# us__2shc.net
KiCad netlist of a schematic drawn in Altium Designer
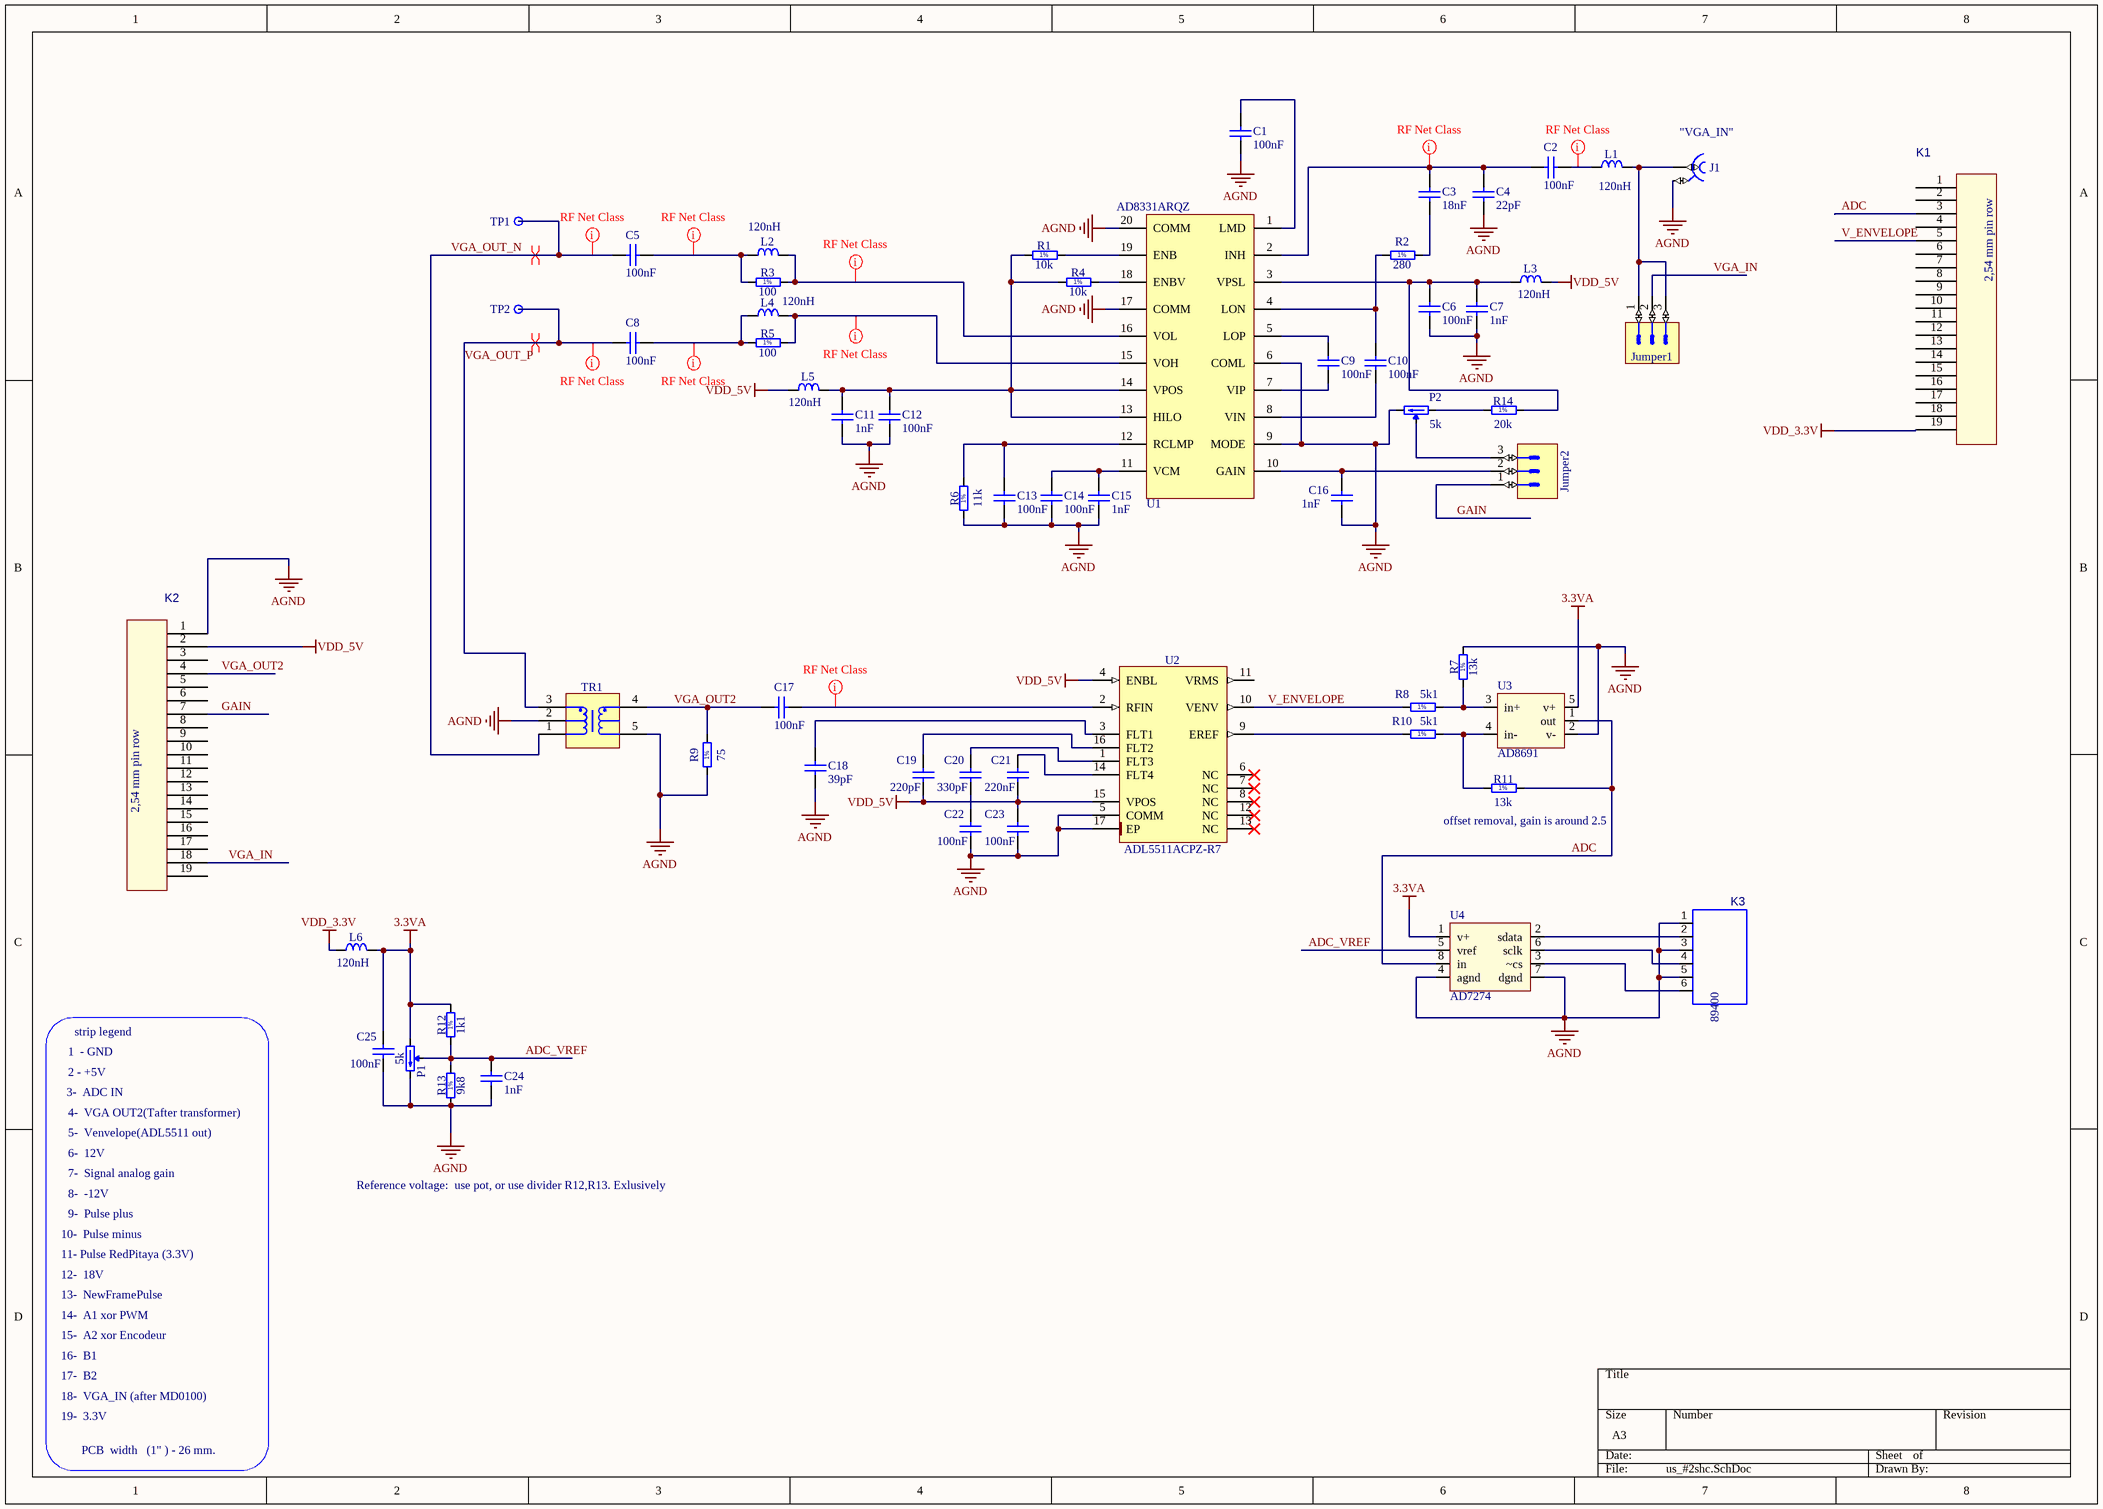
[diagram p0: us_#2shc.SchDoc]

(export (version "E")
  (design (tool "Eeschema 10.0.6"))
  (components
    (comp (ref "C1")
      (value "100nF")
      (footprint "SM0603 _3D_cap")
      (description "Capacitor  0603 inch")
      (fields (field (name "Comment") "cap0603") (field (name "PUBLISHER") "Altium Limited"))
      (libsource (lib "alt_vovan") (part "cap0603"))
    )
    (comp (ref "C2")
      (value "100nF")
      (footprint "SM0603 _3D_cap")
      (description "Capacitor  0603 inch")
      (fields (field (name "Comment") "cap0603") (field (name "PUBLISHER") "Altium Limited"))
      (libsource (lib "alt_vovan") (part "cap0603"))
    )
    (comp (ref "C3")
      (value "18nF")
      (footprint "SM0603 _3D_cap")
      (description "Capacitor  0603 inch")
      (fields (field (name "Comment") "cap0603") (field (name "PUBLISHER") "Altium Limited"))
      (libsource (lib "alt_vovan") (part "cap0603"))
    )
    (comp (ref "C4")
      (value "22pF")
      (footprint "SM0603 _3D_cap")
      (description "Capacitor  0603 inch")
      (fields (field (name "Comment") "cap0603") (field (name "PUBLISHER") "Altium Limited"))
      (libsource (lib "alt_vovan") (part "cap0603"))
    )
    (comp (ref "C5")
      (value "100nF")
      (footprint "SM0603 _3D_cap")
      (description "Capacitor  0603 inch")
      (fields (field (name "Comment") "cap0603") (field (name "PUBLISHER") "Altium Limited"))
      (libsource (lib "alt_vovan") (part "cap0603"))
    )
    (comp (ref "C6")
      (value "100nF")
      (footprint "SM0603 _3D_cap")
      (description "Capacitor  0603 inch")
      (fields (field (name "Comment") "cap0603") (field (name "PUBLISHER") "Altium Limited"))
      (libsource (lib "alt_vovan") (part "cap0603"))
    )
    (comp (ref "C7")
      (value "1nF")
      (footprint "SM0603 _3D_cap")
      (description "Capacitor  0603 inch")
      (fields (field (name "Comment") "cap0603") (field (name "PUBLISHER") "Altium Limited"))
      (libsource (lib "alt_vovan") (part "cap0603"))
    )
    (comp (ref "C8")
      (value "100nF")
      (footprint "SM0603 _3D_cap")
      (description "Capacitor  0603 inch")
      (fields (field (name "Comment") "cap0603") (field (name "PUBLISHER") "Altium Limited"))
      (libsource (lib "alt_vovan") (part "cap0603"))
    )
    (comp (ref "C9")
      (value "100nF")
      (footprint "SM0603 _3D_cap")
      (description "Capacitor  0603 inch")
      (fields (field (name "Comment") "cap0603") (field (name "PUBLISHER") "Altium Limited"))
      (libsource (lib "alt_vovan") (part "cap0603"))
    )
    (comp (ref "C10")
      (value "100nF")
      (footprint "SM0603 _3D_cap")
      (description "Capacitor  0603 inch")
      (fields (field (name "Comment") "cap0603") (field (name "PUBLISHER") "Altium Limited"))
      (libsource (lib "alt_vovan") (part "cap0603"))
    )
    (comp (ref "C11")
      (value "1nF")
      (footprint "SM0603 _3D_cap")
      (description "Capacitor  0603 inch")
      (fields (field (name "Comment") "cap0603") (field (name "PUBLISHER") "Altium Limited"))
      (libsource (lib "alt_vovan") (part "cap0603"))
    )
    (comp (ref "C12")
      (value "100nF")
      (footprint "SM0603 _3D_cap")
      (description "Capacitor  0603 inch")
      (fields (field (name "Comment") "cap0603") (field (name "PUBLISHER") "Altium Limited"))
      (libsource (lib "alt_vovan") (part "cap0603"))
    )
    (comp (ref "C13")
      (value "100nF")
      (footprint "SM0603 _3D_cap")
      (description "Capacitor  0603 inch")
      (fields (field (name "Comment") "cap0603") (field (name "PUBLISHER") "Altium Limited"))
      (libsource (lib "alt_vovan") (part "cap0603"))
    )
    (comp (ref "C14")
      (value "100nF")
      (footprint "SM0603 _3D_cap")
      (description "Capacitor  0603 inch")
      (fields (field (name "Comment") "cap0603") (field (name "PUBLISHER") "Altium Limited"))
      (libsource (lib "alt_vovan") (part "cap0603"))
    )
    (comp (ref "C15")
      (value "1nF")
      (footprint "SM0603 _3D_cap")
      (description "Capacitor  0603 inch")
      (fields (field (name "Comment") "cap0603") (field (name "PUBLISHER") "Altium Limited"))
      (libsource (lib "alt_vovan") (part "cap0603"))
    )
    (comp (ref "C16")
      (value "1nF")
      (footprint "SM0603 _3D_cap")
      (description "Capacitor  0603 inch")
      (fields (field (name "Comment") "cap0603") (field (name "PUBLISHER") "Altium Limited"))
      (libsource (lib "alt_vovan") (part "cap0603"))
    )
    (comp (ref "C17")
      (value "100nF")
      (footprint "SM0603 _3D_cap")
      (description "Capacitor  0603 inch")
      (fields (field (name "Comment") "cap0603") (field (name "PUBLISHER") "Altium Limited"))
      (libsource (lib "alt_vovan") (part "cap0603"))
    )
    (comp (ref "C18")
      (value "39pF")
      (footprint "SM0603 _3D_cap")
      (description "Capacitor  0603 inch")
      (fields (field (name "Comment") "cap0603") (field (name "PUBLISHER") "Altium Limited"))
      (libsource (lib "alt_vovan") (part "cap0603"))
    )
    (comp (ref "C19")
      (value "220pF")
      (footprint "SM0603 _3D_cap")
      (description "Capacitor  0603 inch")
      (fields (field (name "Comment") "cap0603") (field (name "PUBLISHER") "Altium Limited"))
      (libsource (lib "alt_vovan") (part "cap0603"))
    )
    (comp (ref "C20")
      (value "330pF")
      (footprint "SM0603 _3D_cap")
      (description "Capacitor  0603 inch")
      (fields (field (name "Comment") "cap0603") (field (name "PUBLISHER") "Altium Limited"))
      (libsource (lib "alt_vovan") (part "cap0603"))
    )
    (comp (ref "C21")
      (value "220nF")
      (footprint "SM0603 _3D_cap")
      (description "Capacitor  0603 inch")
      (fields (field (name "Comment") "cap0603") (field (name "PUBLISHER") "Altium Limited"))
      (libsource (lib "alt_vovan") (part "cap0603"))
    )
    (comp (ref "C22")
      (value "100nF")
      (footprint "SM0603 _3D_cap")
      (description "Capacitor  0603 inch")
      (fields (field (name "Comment") "cap0603") (field (name "PUBLISHER") "Altium Limited"))
      (libsource (lib "alt_vovan") (part "cap0603"))
    )
    (comp (ref "C23")
      (value "100nF")
      (footprint "SM0603 _3D_cap")
      (description "Capacitor  0603 inch")
      (fields (field (name "Comment") "cap0603") (field (name "PUBLISHER") "Altium Limited"))
      (libsource (lib "alt_vovan") (part "cap0603"))
    )
    (comp (ref "C24")
      (value "1nF")
      (footprint "SM0603 _3D_cap")
      (description "Capacitor  0603 inch")
      (fields (field (name "Comment") "cap0603") (field (name "PUBLISHER") "Altium Limited"))
      (libsource (lib "alt_vovan") (part "cap0603"))
    )
    (comp (ref "C25")
      (value "100nF")
      (footprint "SM0603 _3D_cap")
      (description "Capacitor  0603 inch")
      (fields (field (name "Comment") "cap0603") (field (name "PUBLISHER") "Altium Limited"))
      (libsource (lib "alt_vovan") (part "cap0603"))
    )
    (comp (ref "J1")
      (value "SMA")
      (footprint "AMPHENOL_132357-11")
      (fields
        (field (name "PART NUMBER") "AMPHENOL_132357-11")
        (field (name "MANUFACTURER") "AMPHENOL")
        (field (name "MANUFACTURER PART NUMBER") "132357-11")
        (field (name "AUTHOR") "CERN DEM JLC")
      )
      (libsource (lib "echOpen_ADC_Card") (part "Coax_1Female_1Shield"))
    )
    (comp (ref "Jumper1")
      (value "~")
      (footprint "SULLINS_GRPB031VWVN")
      (description "Connector 3 Male")
      (fields
        (field (name "PART NUMBER") "SULLINS_GRPB031VWVN")
        (field (name "MANUFACTURER") "SULLINS")
        (field (name "AUTHOR") "S. Jafar")
      )
      (libsource (lib "Sof-Connectors") (part "Connector 3 Male"))
    )
    (comp (ref "Jumper2")
      (value "~")
      (footprint "SULLINS_GRPB031VWVN")
      (description "Connector 3 Male")
      (fields
        (field (name "PART NUMBER") "SULLINS_GRPB031VWVN")
        (field (name "MANUFACTURER") "SULLINS")
        (field (name "AUTHOR") "S. Jafar")
      )
      (libsource (lib "") (part "Connector 3 Male_1"))
    )
    (comp (ref "K1")
      (value "PLS_2.54mm-19")
      (footprint "PLS_2.54mm-19")
      (libsource (lib "alt_vovan") (part "PLS_2.54mm-19"))
    )
    (comp (ref "K2")
      (value "PLS_2.54mm-19")
      (footprint "PLS_2.54mm-19")
      (libsource (lib "") (part "PLS_2.54mm-19_1"))
    )
    (comp (ref "K3")
      (value "Molex_89400_061")
      (footprint "Molex_89400-061")
      (description "6 pin vertical 2mm")
      (libsource (lib "alt_vovan") (part "Molex_89400_061"))
    )
    (comp (ref "L1")
      (value "75R@100MHz")
      (footprint "SM_0805_INDUCTANCE _3D")
      (description "chip inductance")
      (fields
        (field (name "PART NUMBER") "IND0805_MURATA_BLM21BB750SN1D")
        (field (name "POWER") "700mA")
        (field (name "AUTHOR") "S. Jafar")
      )
      (libsource (lib "alt_vovan") (part "Ind_Chip"))
    )
    (comp (ref "L2")
      (value "75R@100MHz")
      (footprint "SM_0805_INDUCTANCE _3D")
      (description "chip inductance")
      (fields
        (field (name "PART NUMBER") "IND0805_MURATA_BLM21BB750SN1D")
        (field (name "POWER") "700mA")
        (field (name "AUTHOR") "S. Jafar")
      )
      (libsource (lib "alt_vovan") (part "Ind_Chip"))
    )
    (comp (ref "L3")
      (value "75R@100MHz")
      (footprint "SM_0805_INDUCTANCE _3D")
      (description "chip inductance")
      (fields
        (field (name "PART NUMBER") "IND0805_MURATA_BLM21BB750SN1D")
        (field (name "POWER") "700mA")
        (field (name "AUTHOR") "S. Jafar")
      )
      (libsource (lib "alt_vovan") (part "Ind_Chip"))
    )
    (comp (ref "L4")
      (value "75R@100MHz")
      (footprint "SM_0805_INDUCTANCE _3D")
      (description "chip inductance")
      (fields
        (field (name "PART NUMBER") "IND0805_MURATA_BLM21BB750SN1D")
        (field (name "POWER") "700mA")
        (field (name "AUTHOR") "S. Jafar")
      )
      (libsource (lib "alt_vovan") (part "Ind_Chip"))
    )
    (comp (ref "L5")
      (value "75R@100MHz")
      (footprint "SM_0805_INDUCTANCE _3D")
      (description "chip inductance")
      (fields
        (field (name "PART NUMBER") "IND0805_MURATA_BLM21BB750SN1D")
        (field (name "POWER") "700mA")
        (field (name "AUTHOR") "S. Jafar")
      )
      (libsource (lib "alt_vovan") (part "Ind_Chip"))
    )
    (comp (ref "L6")
      (value "75R@100MHz")
      (footprint "SM_0805_INDUCTANCE _3D")
      (description "chip inductance")
      (fields
        (field (name "PART NUMBER") "IND0805_MURATA_BLM21BB750SN1D")
        (field (name "POWER") "700mA")
        (field (name "AUTHOR") "S. Jafar")
      )
      (libsource (lib "alt_vovan") (part "Ind_Chip"))
    )
    (comp (ref "P1")
      (value "5k")
      (footprint "TRIM_BOURNS_3223W")
      (description "Trimming Potentiometer")
      (fields
        (field (name "PART NUMBER") "TRIM_11T_5K_BOURNS_3223W-1-502E")
        (field (name "POWER") "0.125W")
        (field (name "AUTHOR") "CERN DEM JLC")
      )
      (libsource (lib "echOpen_ADC_Card") (part "Trimming Potentiometer"))
    )
    (comp (ref "P2")
      (value "5k")
      (footprint "TRIM_BOURNS_3223W")
      (description "Trimming Potentiometer")
      (fields
        (field (name "PART NUMBER") "TRIM_11T_5K_BOURNS_3223W-1-502E")
        (field (name "POWER") "0.125W")
        (field (name "AUTHOR") "CERN DEM JLC")
      )
      (libsource (lib "echOpen_ADC_Card") (part "Trimming Potentiometer"))
    )
    (comp (ref "R1")
      (value "10k")
      (footprint "SM0603_3D_res")
      (description "Res_0603_1%_EU")
      (fields
        (field (name "PART NUMBER") "R1206_4K7_1%_0.25W_100PPM")
        (field (name "POWER") "0.25W")
        (field (name "AUTHOR") "CERN DEM JLC")
      )
      (libsource (lib "alt_vovan") (part "Res_0603_1%_EU"))
    )
    (comp (ref "R2")
      (value "280")
      (footprint "SM0603_3D_res")
      (description "Res_0603_1%_EU")
      (fields
        (field (name "PART NUMBER") "R1206_4K7_1%_0.25W_100PPM")
        (field (name "POWER") "0.25W")
        (field (name "AUTHOR") "CERN DEM JLC")
      )
      (libsource (lib "alt_vovan") (part "Res_0603_1%_EU"))
    )
    (comp (ref "R3")
      (value "100")
      (footprint "SM0603_3D_res")
      (description "Res_0603_1%_EU")
      (fields
        (field (name "PART NUMBER") "R1206_4K7_1%_0.25W_100PPM")
        (field (name "POWER") "0.25W")
        (field (name "AUTHOR") "CERN DEM JLC")
      )
      (libsource (lib "alt_vovan") (part "Res_0603_1%_EU"))
    )
    (comp (ref "R4")
      (value "10k")
      (footprint "SM0603_3D_res")
      (description "Res_0603_1%_EU")
      (fields
        (field (name "PART NUMBER") "R1206_4K7_1%_0.25W_100PPM")
        (field (name "POWER") "0.25W")
        (field (name "AUTHOR") "CERN DEM JLC")
      )
      (libsource (lib "alt_vovan") (part "Res_0603_1%_EU"))
    )
    (comp (ref "R5")
      (value "100")
      (footprint "SM0603_3D_res")
      (description "Res_0603_1%_EU")
      (fields
        (field (name "PART NUMBER") "R1206_4K7_1%_0.25W_100PPM")
        (field (name "POWER") "0.25W")
        (field (name "AUTHOR") "CERN DEM JLC")
      )
      (libsource (lib "alt_vovan") (part "Res_0603_1%_EU"))
    )
    (comp (ref "R6")
      (value "11k")
      (footprint "SM0603_3D_res")
      (description "Res_0603_1%_EU")
      (fields
        (field (name "PART NUMBER") "R1206_4K7_1%_0.25W_100PPM")
        (field (name "POWER") "0.25W")
        (field (name "AUTHOR") "CERN DEM JLC")
      )
      (libsource (lib "alt_vovan") (part "Res_0603_1%_EU"))
    )
    (comp (ref "R7")
      (value "13k")
      (footprint "SM0603_3D_res")
      (description "Res_0603_1%_EU")
      (fields
        (field (name "PART NUMBER") "R1206_4K7_1%_0.25W_100PPM")
        (field (name "POWER") "0.25W")
        (field (name "AUTHOR") "CERN DEM JLC")
      )
      (libsource (lib "alt_vovan") (part "Res_0603_1%_EU"))
    )
    (comp (ref "R8")
      (value "5k1")
      (footprint "SM0603_3D_res")
      (description "Res_0603_1%_EU")
      (fields
        (field (name "PART NUMBER") "R1206_4K7_1%_0.25W_100PPM")
        (field (name "POWER") "0.25W")
        (field (name "AUTHOR") "CERN DEM JLC")
      )
      (libsource (lib "alt_vovan") (part "Res_0603_1%_EU"))
    )
    (comp (ref "R9")
      (value "75")
      (footprint "SM0603_3D_res")
      (description "Res_0603_1%_EU")
      (fields
        (field (name "PART NUMBER") "R1206_4K7_1%_0.25W_100PPM")
        (field (name "POWER") "0.25W")
        (field (name "AUTHOR") "CERN DEM JLC")
      )
      (libsource (lib "alt_vovan") (part "Res_0603_1%_EU"))
    )
    (comp (ref "R10")
      (value "5k1")
      (footprint "SM0603_3D_res")
      (description "Res_0603_1%_EU")
      (fields
        (field (name "PART NUMBER") "R1206_4K7_1%_0.25W_100PPM")
        (field (name "POWER") "0.25W")
        (field (name "AUTHOR") "CERN DEM JLC")
      )
      (libsource (lib "alt_vovan") (part "Res_0603_1%_EU"))
    )
    (comp (ref "R11")
      (value "13k")
      (footprint "SM0603_3D_res")
      (description "Res_0603_1%_EU")
      (fields
        (field (name "PART NUMBER") "R1206_4K7_1%_0.25W_100PPM")
        (field (name "POWER") "0.25W")
        (field (name "AUTHOR") "CERN DEM JLC")
      )
      (libsource (lib "alt_vovan") (part "Res_0603_1%_EU"))
    )
    (comp (ref "R12")
      (value "1k1")
      (footprint "SM0603_3D_res")
      (description "Res_0603_1%_EU")
      (fields
        (field (name "PART NUMBER") "R1206_4K7_1%_0.25W_100PPM")
        (field (name "POWER") "0.25W")
        (field (name "AUTHOR") "CERN DEM JLC")
      )
      (libsource (lib "alt_vovan") (part "Res_0603_1%_EU"))
    )
    (comp (ref "R13")
      (value "9k8")
      (footprint "SM0603_3D_res")
      (description "Res_0603_1%_EU")
      (fields
        (field (name "PART NUMBER") "R1206_4K7_1%_0.25W_100PPM")
        (field (name "POWER") "0.25W")
        (field (name "AUTHOR") "CERN DEM JLC")
      )
      (libsource (lib "alt_vovan") (part "Res_0603_1%_EU"))
    )
    (comp (ref "R14")
      (value "20k")
      (footprint "SM0603_3D_res")
      (description "Res_0603_1%_EU")
      (fields
        (field (name "PART NUMBER") "R1206_4K7_1%_0.25W_100PPM")
        (field (name "POWER") "0.25W")
        (field (name "AUTHOR") "CERN DEM JLC")
      )
      (libsource (lib "alt_vovan") (part "Res_0603_1%_EU"))
    )
    (comp (ref "TP1")
      (value "Test Point")
      (footprint "NICOMATIC_C12000B")
      (fields
        (field (name "PART NUMBER") "NICOMATIC_C12000B")
        (field (name "MANUFACTURER") "NICOMATIC")
        (field (name "MANUFACTURER PART NUMBER") "C12000B")
        (field (name "AUTHOR") "CERN DEM JLC")
      )
      (libsource (lib "Sof-Connectors") (part "Test Point"))
    )
    (comp (ref "TP2")
      (value "Test Point")
      (footprint "NICOMATIC_C12000B")
      (fields
        (field (name "PART NUMBER") "NICOMATIC_C12000B")
        (field (name "MANUFACTURER") "NICOMATIC")
        (field (name "MANUFACTURER PART NUMBER") "C12000B")
        (field (name "AUTHOR") "CERN DEM JLC")
      )
      (libsource (lib "Sof-Connectors") (part "Test Point"))
    )
    (comp (ref "TR1")
      (value "1:1")
      (footprint "alt_vovan:Pulse_CX2041NL")
      (description "75 Ohm 0.05 to 300MHz RF Transformers")
      (fields
        (field (name "PART NUMBER") "XFMR_MINI-CIRCUITS_T1-6T-KK81")
        (field (name "MANUFACTURER") "MINI-CIRCUITS")
        (field (name "AUTHOR") "S. Jafar")
      )
      (libsource (lib "alt2017") (part "Pulse_CX2041NL"))
    )
    (comp (ref "U1")
      (value "AD8331ARQZ")
      (footprint "SOP64P600X175-20N")
      (fields (field (name "MANUFACTURER") "Analog Devices") (field (name "AUTHOR") "S. Jafar"))
      (libsource (lib "Sof-ICs And Semiconductors") (part "AD8331"))
    )
    (comp (ref "U2")
      (value "ADL5511ACPZ-R7")
      (footprint "QFN50P300X300X80-17N-S175")
      (description "DC to 6 GHz Envelope and TruPwr RMS Detector")
      (fields (field (name "MANUFACTURER") "ANALOG DEVICES") (field (name "AUTHOR") "CERN DEM JLC"))
      (libsource (lib "Sof-ICs And Semiconductors") (part "ADL5511"))
    )
    (comp (ref "U3")
      (value "AD8691")
      (footprint "TSOT-5(RT-5)")
      (libsource (lib "alt_vovan") (part "OpAmp_TSOT5"))
    )
    (comp (ref "U4")
      (value "AD7274")
      (footprint "RM-8")
      (description "adc serial")
      (libsource (lib "alt_vovan") (part "AD7274"))
    )
  )
  (nets
    (net (code "1") (name "/ADC") (class "Default")
      (node (ref "K1") (pin "3") (pinfunction "3_3") (pintype "passive"))
      (node (ref "R11") (pin "2") (pinfunction "2_2") (pintype "passive"))
      (node (ref "U3") (pin "1") (pinfunction "out_1") (pintype "passive"))
      (node (ref "U4") (pin "8") (pinfunction "in_8") (pintype "passive"))
    )
    (net (code "2") (name "/ADC_VREF") (class "Default")
      (node (ref "C24") (pin "2") (pinfunction "2_2") (pintype "passive"))
      (node (ref "P1") (pin "2") (pinfunction "W_2") (pintype "passive"))
      (node (ref "R12") (pin "1") (pinfunction "1_1") (pintype "passive"))
      (node (ref "R13") (pin "2") (pinfunction "2_2") (pintype "passive"))
      (node (ref "U4") (pin "5") (pinfunction "vref_5") (pintype "passive"))
    )
    (net (code "3") (name "/GAIN") (class "Default")
      (node (ref "Jumper2") (pin "1") (pinfunction "1_1") (pintype "bidirectional"))
      (node (ref "K2") (pin "7") (pinfunction "7_7") (pintype "passive"))
    )
    (net (code "4") (name "/VGA_IN") (class "Default")
      (node (ref "Jumper1") (pin "2") (pinfunction "2_2") (pintype "bidirectional"))
      (node (ref "K2") (pin "18") (pinfunction "18_18") (pintype "passive"))
    )
    (net (code "5") (name "/VGA_OUT2") (class "Default")
      (node (ref "C17") (pin "1") (pinfunction "1_1") (pintype "passive"))
      (node (ref "K2") (pin "4") (pinfunction "4_4") (pintype "passive"))
      (node (ref "R9") (pin "2") (pinfunction "2_2") (pintype "passive"))
      (node (ref "TR1") (pin "4") (pinfunction "SDOT_4") (pintype "passive"))
    )
    (net (code "6") (name "/VGA_OUT_N") (class "Default")
      (node (ref "C5") (pin "1") (pinfunction "1_1") (pintype "passive"))
      (node (ref "TP1") (pin "1") (pinfunction "1_1") (pintype "bidirectional"))
      (node (ref "TR1") (pin "1") (pinfunction "P_1") (pintype "passive"))
    )
    (net (code "7") (name "/VGA_OUT_P") (class "Default")
      (node (ref "C8") (pin "2") (pinfunction "2_2") (pintype "passive"))
      (node (ref "TP2") (pin "1") (pinfunction "1_1") (pintype "bidirectional"))
      (node (ref "TR1") (pin "3") (pinfunction "PDOT_3") (pintype "passive"))
    )
    (net (code "8") (name "/V_ENVELOPE") (class "Default")
      (node (ref "K1") (pin "5") (pinfunction "5_5") (pintype "passive"))
      (node (ref "R8") (pin "1") (pinfunction "1_1") (pintype "passive"))
      (node (ref "U2") (pin "10") (pinfunction "VENV_10") (pintype "output"))
    )
    (net (code "9") (name "3.3VA") (class "Default")
      (node (ref "C25") (pin "2") (pinfunction "2_2") (pintype "passive"))
      (node (ref "L6") (pin "2") (pinfunction "2_2") (pintype "passive"))
      (node (ref "P1") (pin "1") (pinfunction "CCW_1") (pintype "passive"))
      (node (ref "R12") (pin "2") (pinfunction "2_2") (pintype "passive"))
      (node (ref "U3") (pin "5") (pinfunction "v+_5") (pintype "passive"))
      (node (ref "U4") (pin "1") (pinfunction "v+_1") (pintype "passive"))
    )
    (net (code "10") (name "AGND") (class "Default")
      (node (ref "C1") (pin "1") (pinfunction "1_1") (pintype "passive"))
      (node (ref "C11") (pin "1") (pinfunction "1_1") (pintype "passive"))
      (node (ref "C12") (pin "1") (pinfunction "1_1") (pintype "passive"))
      (node (ref "C13") (pin "1") (pinfunction "1_1") (pintype "passive"))
      (node (ref "C14") (pin "1") (pinfunction "1_1") (pintype "passive"))
      (node (ref "C15") (pin "1") (pinfunction "1_1") (pintype "passive"))
      (node (ref "C16") (pin "1") (pinfunction "1_1") (pintype "passive"))
      (node (ref "C18") (pin "1") (pinfunction "1_1") (pintype "passive"))
      (node (ref "C22") (pin "1") (pinfunction "1_1") (pintype "passive"))
      (node (ref "C23") (pin "1") (pinfunction "1_1") (pintype "passive"))
      (node (ref "C24") (pin "1") (pinfunction "1_1") (pintype "passive"))
      (node (ref "C25") (pin "1") (pinfunction "1_1") (pintype "passive"))
      (node (ref "C4") (pin "1") (pinfunction "1_1") (pintype "passive"))
      (node (ref "C6") (pin "1") (pinfunction "1_1") (pintype "passive"))
      (node (ref "C7") (pin "1") (pinfunction "1_1") (pintype "passive"))
      (node (ref "J1") (pin "2") (pinfunction "2_2") (pintype "bidirectional"))
      (node (ref "K2") (pin "1") (pinfunction "1_1") (pintype "passive"))
      (node (ref "K3") (pin "1") (pinfunction "1_1") (pintype "passive"))
      (node (ref "K3") (pin "3") (pinfunction "3_3") (pintype "passive"))
      (node (ref "K3") (pin "5") (pinfunction "5_5") (pintype "passive"))
      (node (ref "P1") (pin "3") (pinfunction "CW_3") (pintype "passive"))
      (node (ref "P2") (pin "3") (pinfunction "CW_3") (pintype "passive"))
      (node (ref "R13") (pin "1") (pinfunction "1_1") (pintype "passive"))
      (node (ref "R6") (pin "1") (pinfunction "1_1") (pintype "passive"))
      (node (ref "R7") (pin "2") (pinfunction "2_2") (pintype "passive"))
      (node (ref "R9") (pin "1") (pinfunction "1_1") (pintype "passive"))
      (node (ref "TR1") (pin "2") (pinfunction "NC_2") (pintype "passive"))
      (node (ref "TR1") (pin "5") (pinfunction "6_5") (pintype "passive"))
      (node (ref "U1") (pin "17") (pinfunction "COMM_17") (pintype "passive"))
      (node (ref "U1") (pin "20") (pinfunction "COMM_20") (pintype "passive"))
      (node (ref "U1") (pin "6") (pinfunction "COML_6") (pintype "passive"))
      (node (ref "U1") (pin "9") (pinfunction "MODE_9") (pintype "passive"))
      (node (ref "U2") (pin "17") (pinfunction "EP_17") (pintype "power_in"))
      (node (ref "U2") (pin "5") (pinfunction "COMM_5") (pintype "power_in"))
      (node (ref "U3") (pin "2") (pinfunction "v-_2") (pintype "passive"))
      (node (ref "U4") (pin "4") (pinfunction "agnd_4") (pintype "passive"))
      (node (ref "U4") (pin "7") (pinfunction "dgnd_7") (pintype "passive"))
    )
    (net (code "11") (name "Net-(C2-Pad2)") (class "Default")
      (node (ref "C2") (pin "2") (pinfunction "2_2") (pintype "passive"))
      (node (ref "L1") (pin "1") (pinfunction "1_1") (pintype "passive"))
    )
    (net (code "12") (name "Net-(C3-Pad1)") (class "Default")
      (node (ref "C3") (pin "1") (pinfunction "1_1") (pintype "passive"))
      (node (ref "R2") (pin "2") (pinfunction "2_2") (pintype "passive"))
    )
    (net (code "13") (name "Net-(C5-Pad2)") (class "Default")
      (node (ref "C5") (pin "2") (pinfunction "2_2") (pintype "passive"))
      (node (ref "L2") (pin "1") (pinfunction "1_1") (pintype "passive"))
      (node (ref "R3") (pin "1") (pinfunction "1_1") (pintype "passive"))
    )
    (net (code "14") (name "Net-(C8-Pad1)") (class "Default")
      (node (ref "C8") (pin "1") (pinfunction "1_1") (pintype "passive"))
      (node (ref "L4") (pin "1") (pinfunction "1_1") (pintype "passive"))
      (node (ref "R5") (pin "1") (pinfunction "1_1") (pintype "passive"))
    )
    (net (code "15") (name "Net-(C20-Pad1)") (class "Default")
      (node (ref "C20") (pin "1") (pinfunction "1_1") (pintype "passive"))
      (node (ref "C22") (pin "2") (pinfunction "2_2") (pintype "passive"))
    )
    (net (code "16") (name "Net-(J1-Pad1)") (class "Default")
      (node (ref "J1") (pin "1") (pinfunction "1_1") (pintype "bidirectional"))
      (node (ref "Jumper1") (pin "1") (pinfunction "1_1") (pintype "bidirectional"))
      (node (ref "Jumper1") (pin "3") (pinfunction "3_3") (pintype "bidirectional"))
      (node (ref "L1") (pin "2") (pinfunction "2_2") (pintype "passive"))
    )
    (net (code "17") (name "Net-(P2-CCW)") (class "Default")
      (node (ref "P2") (pin "1") (pinfunction "CCW_1") (pintype "passive"))
      (node (ref "R14") (pin "1") (pinfunction "1_1") (pintype "passive"))
    )
    (net (code "18") (name "Net-(P2-W)") (class "Default")
      (node (ref "Jumper2") (pin "3") (pinfunction "3_3") (pintype "bidirectional"))
      (node (ref "P2") (pin "2") (pinfunction "W_2") (pintype "passive"))
    )
    (net (code "19") (name "Net-(U1-ENB)") (class "Default")
      (node (ref "R1") (pin "2") (pinfunction "2_2") (pintype "passive"))
      (node (ref "U1") (pin "19") (pinfunction "ENB_19") (pintype "passive"))
    )
    (net (code "20") (name "Net-(U1-ENBV)") (class "Default")
      (node (ref "R4") (pin "2") (pinfunction "2_2") (pintype "passive"))
      (node (ref "U1") (pin "18") (pinfunction "ENBV_18") (pintype "passive"))
    )
    (net (code "21") (name "Net-(U1-GAIN)") (class "Default")
      (node (ref "C16") (pin "2") (pinfunction "2_2") (pintype "passive"))
      (node (ref "Jumper2") (pin "2") (pinfunction "2_2") (pintype "bidirectional"))
      (node (ref "U1") (pin "10") (pinfunction "GAIN_10") (pintype "passive"))
    )
    (net (code "22") (name "Net-(U1-HILO)") (class "Default")
      (node (ref "C11") (pin "2") (pinfunction "2_2") (pintype "passive"))
      (node (ref "C12") (pin "2") (pinfunction "2_2") (pintype "passive"))
      (node (ref "L5") (pin "2") (pinfunction "2_2") (pintype "passive"))
      (node (ref "R1") (pin "1") (pinfunction "1_1") (pintype "passive"))
      (node (ref "R4") (pin "1") (pinfunction "1_1") (pintype "passive"))
      (node (ref "U1") (pin "13") (pinfunction "HILO_13") (pintype "passive"))
      (node (ref "U1") (pin "14") (pinfunction "VPOS_14") (pintype "passive"))
    )
    (net (code "23") (name "Net-(U1-INH)") (class "Default")
      (node (ref "C2") (pin "1") (pinfunction "1_1") (pintype "passive"))
      (node (ref "C3") (pin "2") (pinfunction "2_2") (pintype "passive"))
      (node (ref "C4") (pin "2") (pinfunction "2_2") (pintype "passive"))
      (node (ref "U1") (pin "2") (pinfunction "INH_2") (pintype "passive"))
    )
    (net (code "24") (name "Net-(U1-LMD)") (class "Default")
      (node (ref "C1") (pin "2") (pinfunction "2_2") (pintype "passive"))
      (node (ref "U1") (pin "1") (pinfunction "LMD_1") (pintype "passive"))
    )
    (net (code "25") (name "Net-(U1-LON)") (class "Default")
      (node (ref "C10") (pin "2") (pinfunction "2_2") (pintype "passive"))
      (node (ref "R2") (pin "1") (pinfunction "1_1") (pintype "passive"))
      (node (ref "U1") (pin "4") (pinfunction "LON_4") (pintype "passive"))
    )
    (net (code "26") (name "Net-(U1-LOP)") (class "Default")
      (node (ref "C9") (pin "2") (pinfunction "2_2") (pintype "passive"))
      (node (ref "U1") (pin "5") (pinfunction "LOP_5") (pintype "passive"))
    )
    (net (code "27") (name "Net-(U1-RCLMP)") (class "Default")
      (node (ref "C13") (pin "2") (pinfunction "2_2") (pintype "passive"))
      (node (ref "R6") (pin "2") (pinfunction "2_2") (pintype "passive"))
      (node (ref "U1") (pin "12") (pinfunction "RCLMP_12") (pintype "passive"))
    )
    (net (code "28") (name "Net-(U1-VCM)") (class "Default")
      (node (ref "C14") (pin "2") (pinfunction "2_2") (pintype "passive"))
      (node (ref "C15") (pin "2") (pinfunction "2_2") (pintype "passive"))
      (node (ref "U1") (pin "11") (pinfunction "VCM_11") (pintype "passive"))
    )
    (net (code "29") (name "Net-(U1-VIN)") (class "Default")
      (node (ref "C10") (pin "1") (pinfunction "1_1") (pintype "passive"))
      (node (ref "U1") (pin "8") (pinfunction "VIN_8") (pintype "passive"))
    )
    (net (code "30") (name "Net-(U1-VIP)") (class "Default")
      (node (ref "C9") (pin "1") (pinfunction "1_1") (pintype "passive"))
      (node (ref "U1") (pin "7") (pinfunction "VIP_7") (pintype "passive"))
    )
    (net (code "31") (name "Net-(U1-VOH)") (class "Default")
      (node (ref "L4") (pin "2") (pinfunction "2_2") (pintype "passive"))
      (node (ref "R5") (pin "2") (pinfunction "2_2") (pintype "passive"))
      (node (ref "U1") (pin "15") (pinfunction "VOH_15") (pintype "passive"))
    )
    (net (code "32") (name "Net-(U1-VOL)") (class "Default")
      (node (ref "L2") (pin "2") (pinfunction "2_2") (pintype "passive"))
      (node (ref "R3") (pin "2") (pinfunction "2_2") (pintype "passive"))
      (node (ref "U1") (pin "16") (pinfunction "VOL_16") (pintype "passive"))
    )
    (net (code "33") (name "Net-(U1-VPSL)") (class "Default")
      (node (ref "C6") (pin "2") (pinfunction "2_2") (pintype "passive"))
      (node (ref "C7") (pin "2") (pinfunction "2_2") (pintype "passive"))
      (node (ref "L3") (pin "1") (pinfunction "1_1") (pintype "passive"))
      (node (ref "R14") (pin "2") (pinfunction "2_2") (pintype "passive"))
      (node (ref "U1") (pin "3") (pinfunction "VPSL_3") (pintype "passive"))
    )
    (net (code "34") (name "Net-(U2-EREF)") (class "Default")
      (node (ref "R10") (pin "1") (pinfunction "1_1") (pintype "passive"))
      (node (ref "U2") (pin "9") (pinfunction "EREF_9") (pintype "output"))
    )
    (net (code "35") (name "Net-(U2-FLT1)") (class "Default")
      (node (ref "C18") (pin "2") (pinfunction "2_2") (pintype "passive"))
      (node (ref "U2") (pin "3") (pinfunction "FLT1_3") (pintype "passive"))
    )
    (net (code "36") (name "Net-(U2-FLT2)") (class "Default")
      (node (ref "C19") (pin "2") (pinfunction "2_2") (pintype "passive"))
      (node (ref "U2") (pin "16") (pinfunction "FLT2_16") (pintype "passive"))
    )
    (net (code "37") (name "Net-(U2-FLT3)") (class "Default")
      (node (ref "C20") (pin "2") (pinfunction "2_2") (pintype "passive"))
      (node (ref "U2") (pin "1") (pinfunction "FLT3_1") (pintype "passive"))
    )
    (net (code "38") (name "Net-(U2-FLT4)") (class "Default")
      (node (ref "C21") (pin "2") (pinfunction "2_2") (pintype "passive"))
      (node (ref "U2") (pin "14") (pinfunction "FLT4_14") (pintype "passive"))
    )
    (net (code "39") (name "Net-(U2-RFIN)") (class "Default")
      (node (ref "C17") (pin "2") (pinfunction "2_2") (pintype "passive"))
      (node (ref "U2") (pin "2") (pinfunction "RFIN_2") (pintype "input"))
    )
    (net (code "40") (name "Net-(U3-in+)") (class "Default")
      (node (ref "R7") (pin "1") (pinfunction "1_1") (pintype "passive"))
      (node (ref "R8") (pin "2") (pinfunction "2_2") (pintype "passive"))
      (node (ref "U3") (pin "3") (pinfunction "in+_3") (pintype "passive"))
    )
    (net (code "41") (name "Net-(U3-in-)") (class "Default")
      (node (ref "R10") (pin "2") (pinfunction "2_2") (pintype "passive"))
      (node (ref "R11") (pin "1") (pinfunction "1_1") (pintype "passive"))
      (node (ref "U3") (pin "4") (pinfunction "in-_4") (pintype "passive"))
    )
    (net (code "42") (name "Net-(U4-sclk)") (class "Default")
      (node (ref "K3") (pin "4") (pinfunction "4_4") (pintype "passive"))
      (node (ref "U4") (pin "6") (pinfunction "sclk_6") (pintype "passive"))
    )
    (net (code "43") (name "Net-(U4-sdata)") (class "Default")
      (node (ref "K3") (pin "2") (pinfunction "2_2") (pintype "passive"))
      (node (ref "U4") (pin "2") (pinfunction "sdata_2") (pintype "passive"))
    )
    (net (code "44") (name "Net-(U4-~cs)") (class "Default")
      (node (ref "K3") (pin "6") (pinfunction "6_6") (pintype "passive"))
      (node (ref "U4") (pin "3") (pinfunction "~cs_3") (pintype "passive"))
    )
    (net (code "45") (name "VDD_3.3V") (class "Default")
      (node (ref "K1") (pin "19") (pinfunction "19_19") (pintype "passive"))
      (node (ref "L6") (pin "1") (pinfunction "1_1") (pintype "passive"))
    )
    (net (code "46") (name "VDD_5V") (class "Default")
      (node (ref "C19") (pin "1") (pinfunction "1_1") (pintype "passive"))
      (node (ref "C21") (pin "1") (pinfunction "1_1") (pintype "passive"))
      (node (ref "C23") (pin "2") (pinfunction "2_2") (pintype "passive"))
      (node (ref "K2") (pin "2") (pinfunction "2_2") (pintype "passive"))
      (node (ref "L3") (pin "2") (pinfunction "2_2") (pintype "passive"))
      (node (ref "L5") (pin "1") (pinfunction "1_1") (pintype "passive"))
      (node (ref "U2") (pin "15") (pinfunction "VPOS_15") (pintype "power_in"))
      (node (ref "U2") (pin "4") (pinfunction "ENBL_4") (pintype "input"))
    )
    (net (code "47") (name "unconnected-(K1-Pad1)") (class "Default")
      (node (ref "K1") (pin "1") (pinfunction "1_1") (pintype "passive"))
    )
    (net (code "48") (name "unconnected-(K1-Pad2)") (class "Default")
      (node (ref "K1") (pin "2") (pinfunction "2_2") (pintype "passive"))
    )
    (net (code "49") (name "unconnected-(K1-Pad4)") (class "Default")
      (node (ref "K1") (pin "4") (pinfunction "4_4") (pintype "passive"))
    )
    (net (code "50") (name "unconnected-(K1-Pad6)") (class "Default")
      (node (ref "K1") (pin "6") (pinfunction "6_6") (pintype "passive"))
    )
    (net (code "51") (name "unconnected-(K1-Pad7)") (class "Default")
      (node (ref "K1") (pin "7") (pinfunction "7_7") (pintype "passive"))
    )
    (net (code "52") (name "unconnected-(K1-Pad8)") (class "Default")
      (node (ref "K1") (pin "8") (pinfunction "8_8") (pintype "passive"))
    )
    (net (code "53") (name "unconnected-(K1-Pad9)") (class "Default")
      (node (ref "K1") (pin "9") (pinfunction "9_9") (pintype "passive"))
    )
    (net (code "54") (name "unconnected-(K1-Pad10)") (class "Default")
      (node (ref "K1") (pin "10") (pinfunction "10_10") (pintype "passive"))
    )
    (net (code "55") (name "unconnected-(K1-Pad11)") (class "Default")
      (node (ref "K1") (pin "11") (pinfunction "11_11") (pintype "passive"))
    )
    (net (code "56") (name "unconnected-(K1-Pad12)") (class "Default")
      (node (ref "K1") (pin "12") (pinfunction "12_12") (pintype "passive"))
    )
    (net (code "57") (name "unconnected-(K1-Pad13)") (class "Default")
      (node (ref "K1") (pin "13") (pinfunction "13_13") (pintype "passive"))
    )
    (net (code "58") (name "unconnected-(K1-Pad14)") (class "Default")
      (node (ref "K1") (pin "14") (pinfunction "14_14") (pintype "passive"))
    )
    (net (code "59") (name "unconnected-(K1-Pad15)") (class "Default")
      (node (ref "K1") (pin "15") (pinfunction "15_15") (pintype "passive"))
    )
    (net (code "60") (name "unconnected-(K1-Pad16)") (class "Default")
      (node (ref "K1") (pin "16") (pinfunction "16_16") (pintype "passive"))
    )
    (net (code "61") (name "unconnected-(K1-Pad17)") (class "Default")
      (node (ref "K1") (pin "17") (pinfunction "17_17") (pintype "passive"))
    )
    (net (code "62") (name "unconnected-(K1-Pad18)") (class "Default")
      (node (ref "K1") (pin "18") (pinfunction "18_18") (pintype "passive"))
    )
    (net (code "63") (name "unconnected-(K2-Pad3)") (class "Default")
      (node (ref "K2") (pin "3") (pinfunction "3_3") (pintype "passive"))
    )
    (net (code "64") (name "unconnected-(K2-Pad5)") (class "Default")
      (node (ref "K2") (pin "5") (pinfunction "5_5") (pintype "passive"))
    )
    (net (code "65") (name "unconnected-(K2-Pad6)") (class "Default")
      (node (ref "K2") (pin "6") (pinfunction "6_6") (pintype "passive"))
    )
    (net (code "66") (name "unconnected-(K2-Pad8)") (class "Default")
      (node (ref "K2") (pin "8") (pinfunction "8_8") (pintype "passive"))
    )
    (net (code "67") (name "unconnected-(K2-Pad9)") (class "Default")
      (node (ref "K2") (pin "9") (pinfunction "9_9") (pintype "passive"))
    )
    (net (code "68") (name "unconnected-(K2-Pad10)") (class "Default")
      (node (ref "K2") (pin "10") (pinfunction "10_10") (pintype "passive"))
    )
    (net (code "69") (name "unconnected-(K2-Pad11)") (class "Default")
      (node (ref "K2") (pin "11") (pinfunction "11_11") (pintype "passive"))
    )
    (net (code "70") (name "unconnected-(K2-Pad12)") (class "Default")
      (node (ref "K2") (pin "12") (pinfunction "12_12") (pintype "passive"))
    )
    (net (code "71") (name "unconnected-(K2-Pad13)") (class "Default")
      (node (ref "K2") (pin "13") (pinfunction "13_13") (pintype "passive"))
    )
    (net (code "72") (name "unconnected-(K2-Pad14)") (class "Default")
      (node (ref "K2") (pin "14") (pinfunction "14_14") (pintype "passive"))
    )
    (net (code "73") (name "unconnected-(K2-Pad15)") (class "Default")
      (node (ref "K2") (pin "15") (pinfunction "15_15") (pintype "passive"))
    )
    (net (code "74") (name "unconnected-(K2-Pad16)") (class "Default")
      (node (ref "K2") (pin "16") (pinfunction "16_16") (pintype "passive"))
    )
    (net (code "75") (name "unconnected-(K2-Pad17)") (class "Default")
      (node (ref "K2") (pin "17") (pinfunction "17_17") (pintype "passive"))
    )
    (net (code "76") (name "unconnected-(K2-Pad19)") (class "Default")
      (node (ref "K2") (pin "19") (pinfunction "19_19") (pintype "passive"))
    )
    (net (code "77") (name "unconnected-(U2-NC-Pad6)") (class "Default")
      (node (ref "U2") (pin "6") (pinfunction "NC_6") (pintype "passive+no_connect"))
    )
    (net (code "78") (name "unconnected-(U2-NC-Pad7)") (class "Default")
      (node (ref "U2") (pin "7") (pinfunction "NC_7") (pintype "passive+no_connect"))
    )
    (net (code "79") (name "unconnected-(U2-NC-Pad8)") (class "Default")
      (node (ref "U2") (pin "8") (pinfunction "NC_8") (pintype "passive+no_connect"))
    )
    (net (code "80") (name "unconnected-(U2-NC-Pad12)") (class "Default")
      (node (ref "U2") (pin "12") (pinfunction "NC_12") (pintype "passive+no_connect"))
    )
    (net (code "81") (name "unconnected-(U2-NC-Pad13)") (class "Default")
      (node (ref "U2") (pin "13") (pinfunction "NC_13") (pintype "passive+no_connect"))
    )
    (net (code "82") (name "unconnected-(U2-VRMS-Pad11)") (class "Default")
      (node (ref "U2") (pin "11") (pinfunction "VRMS_11") (pintype "output"))
    )
  )
)
